# GEMINI.net
KiCad netlist of a schematic drawn in EAGLE
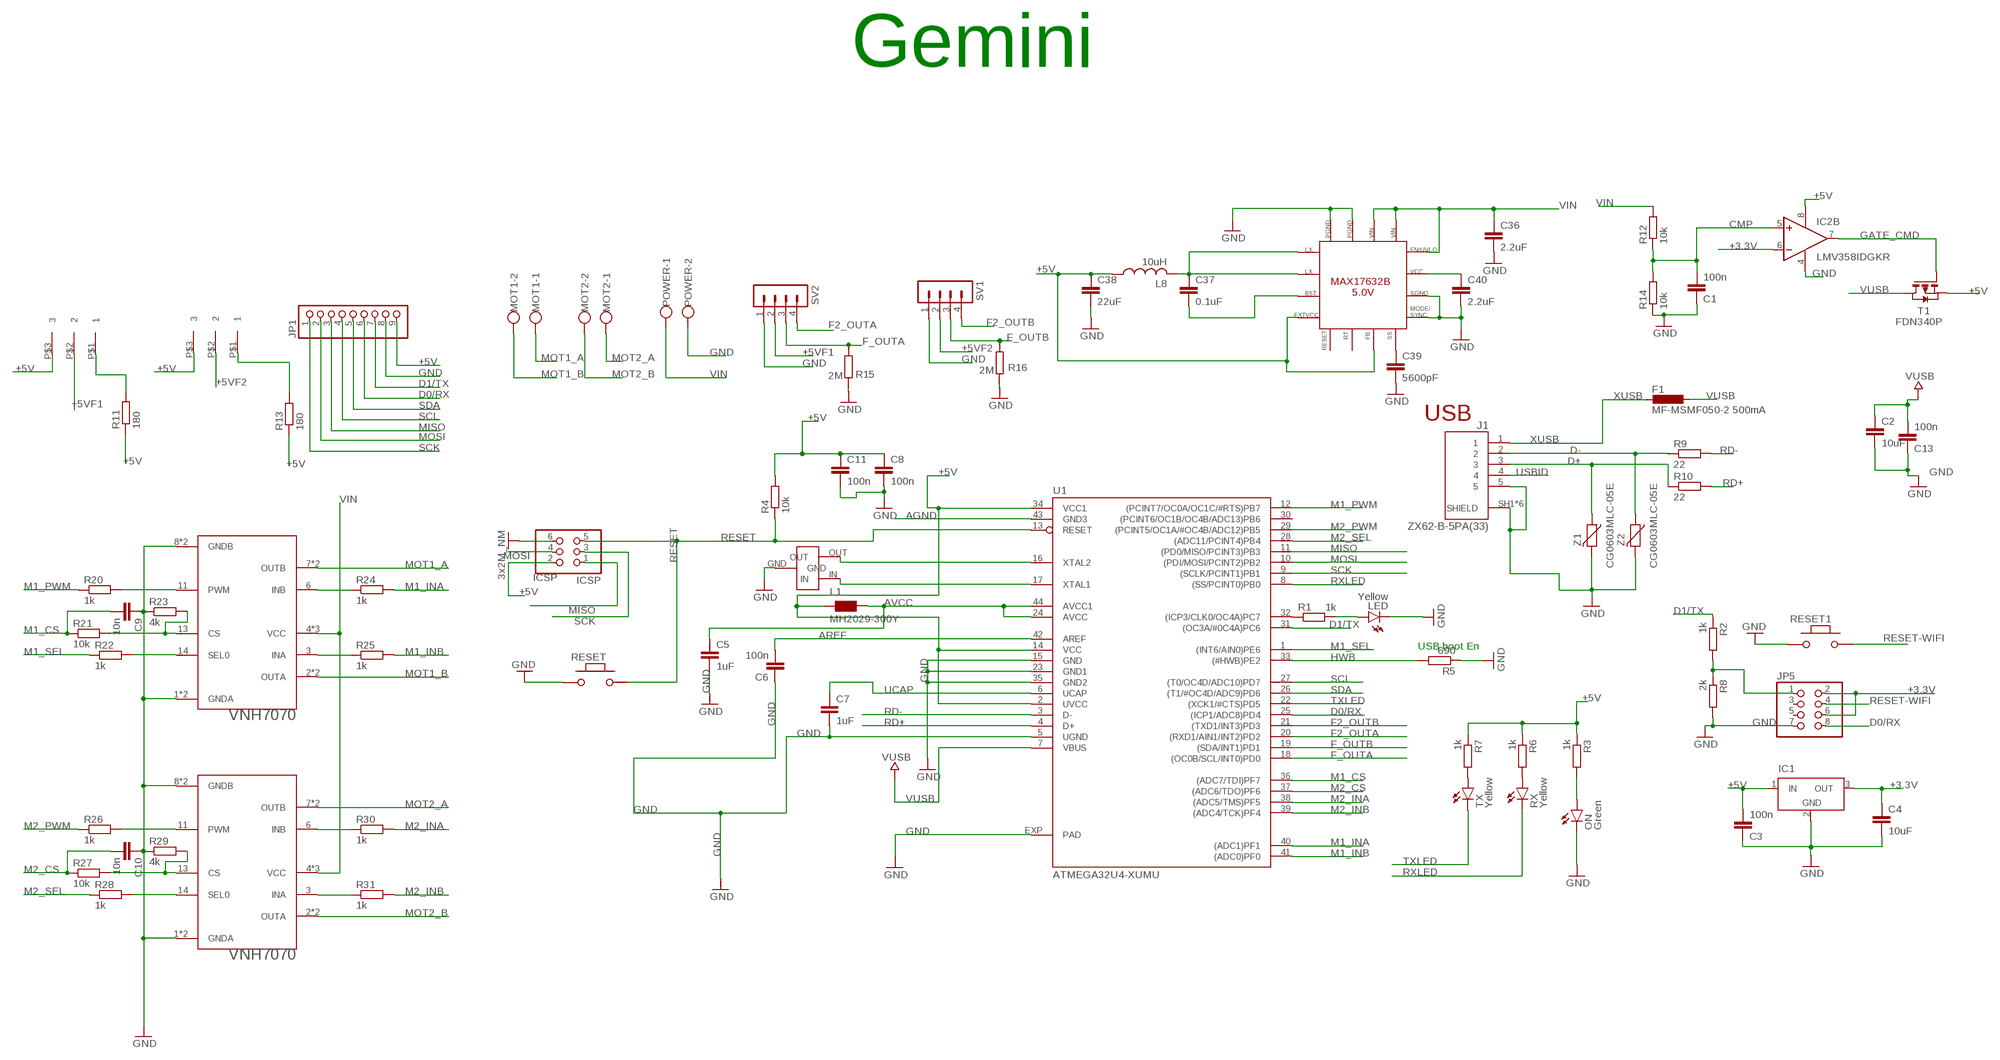
[diagram p0: schematic, sheet 1]

(export (version "E")
  (design (tool "Eeschema 10.0.6"))
  (components
    (comp (ref "C1")
      (value "100n")
      (footprint "eagle-import:C0402K")
      (libsource (lib "eagle-import") (part "rcl_334_C-EUC0402K"))
    )
    (comp (ref "C2")
      (value "10uF")
      (footprint "eagle-import:C0805")
      (libsource (lib "eagle-import") (part "rcl_334_C-EUC0805"))
    )
    (comp (ref "C3")
      (value "100n")
      (footprint "eagle-import:C0402K")
      (libsource (lib "eagle-import") (part "rcl_334_C-EUC0402K"))
    )
    (comp (ref "C4")
      (value "10uF")
      (footprint "eagle-import:C0805")
      (libsource (lib "eagle-import") (part "rcl_334_C-EUC0805"))
    )
    (comp (ref "C5")
      (value "1uF")
      (footprint "eagle-import:C0603-ROUND")
      (libsource (lib "eagle-import") (part "C-EUC0603"))
    )
    (comp (ref "C6")
      (value "100n")
      (footprint "eagle-import:C0402K")
      (libsource (lib "eagle-import") (part "rcl_334_C-EUC0402K"))
    )
    (comp (ref "C7")
      (value "1uF")
      (footprint "eagle-import:C0603-ROUND")
      (libsource (lib "eagle-import") (part "C-EUC0603"))
    )
    (comp (ref "C8")
      (value "100n")
      (footprint "eagle-import:C0402K")
      (libsource (lib "eagle-import") (part "rcl_334_C-EUC0402K"))
    )
    (comp (ref "C9")
      (value "10n")
      (footprint "eagle-import:C0402")
      (libsource (lib "eagle-import") (part "CC0402"))
    )
    (comp (ref "C10")
      (value "10n")
      (footprint "eagle-import:C0402")
      (libsource (lib "eagle-import") (part "CC0402"))
    )
    (comp (ref "C11")
      (value "100n")
      (footprint "eagle-import:C0402K")
      (libsource (lib "eagle-import") (part "rcl_334_C-EUC0402K"))
    )
    (comp (ref "C13")
      (value "100n")
      (footprint "eagle-import:C0402K")
      (libsource (lib "eagle-import") (part "rcl_334_C-EUC0402K"))
    )
    (comp (ref "C36")
      (value "2.2uF")
      (footprint "eagle-import:C0805")
      (libsource (lib "eagle-import") (part "rcl_334_C-EUC0805"))
    )
    (comp (ref "C37")
      (value "0.1uF")
      (footprint "eagle-import:C0805")
      (libsource (lib "eagle-import") (part "rcl_334_C-EUC0805"))
    )
    (comp (ref "C38")
      (value "22uF")
      (footprint "eagle-import:C0805")
      (libsource (lib "eagle-import") (part "rcl_334_C-EUC0805"))
    )
    (comp (ref "C39")
      (value "5600pF")
      (footprint "eagle-import:C0805")
      (libsource (lib "eagle-import") (part "rcl_334_C-EUC0805"))
    )
    (comp (ref "C40")
      (value "2.2uF")
      (footprint "eagle-import:C0805")
      (libsource (lib "eagle-import") (part "rcl_334_C-EUC0805"))
    )
    (comp (ref "F1")
      (value "MF-MSMF050-2 500mA")
      (footprint "eagle-import:L1812")
      (libsource (lib "eagle-import") (part "L-EUL1812"))
    )
    (comp (ref "IC1")
      (value "LT1129CST5")
      (footprint "eagle-import:SOT223")
      (fields (field (name "MPN") "LT1129CST-5#PBF"))
      (libsource (lib "eagle-import") (part "LT1129CST5"))
    )
    (comp (ref "IC2")
      (value "LMV358IDGKR")
      (footprint "eagle-import:MSOP08")
      (libsource (lib "eagle-import") (part "LMV358?MMX"))
    )
    (comp (ref "ICSP")
      (value "ICSP")
      (footprint "eagle-import:2X03")
      (libsource (lib "eagle-import") (part "PINHD-2X3"))
    )
    (comp (ref "J1")
      (value "ZX62-B-5PA(33)")
      (footprint "eagle-import:HRS_ZX62-B-5PA(33)")
      (fields (field (name "MF") "Hirose") (field (name "MP") "ZX62-B-5PA_33_"))
      (libsource (lib "eagle-import") (part "ZX62-B-5PA(33)"))
    )
    (comp (ref "JP1")
      (value "PINHD-1X9")
      (footprint "eagle-import:1X09-BIG")
      (libsource (lib "eagle-import") (part "PINHD-1X9"))
    )
    (comp (ref "JP5")
      (value "PINHD-2X4")
      (footprint "eagle-import:2X04")
      (libsource (lib "eagle-import") (part "PINHD-2X4"))
    )
    (comp (ref "L1")
      (value "MH2029-300Y")
      (footprint "eagle-import:0805")
      (libsource (lib "eagle-import") (part "WE-CBF_0805"))
    )
    (comp (ref "L8")
      (value "10uH")
      (footprint "eagle-import:RCL_L1812")
      (libsource (lib "eagle-import") (part "RCL_L-USL1812"))
    )
    (comp (ref "LED")
      (value "Yellow")
      (footprint "eagle-import:CHIPLED_0805")
      (libsource (lib "eagle-import") (part "LEDCHIPLED_0805"))
    )
    (comp (ref "MOT1")
      (value "W237-102")
      (footprint "eagle-import:W237-102")
      (fields (field (name "MPN") "237-102"))
      (libsource (lib "eagle-import") (part "W237-102"))
    )
    (comp (ref "MOT2")
      (value "W237-102")
      (footprint "eagle-import:W237-102")
      (fields (field (name "MPN") "237-102"))
      (libsource (lib "eagle-import") (part "W237-102"))
    )
    (comp (ref "ON")
      (value "Green")
      (footprint "eagle-import:CHIPLED_0805")
      (libsource (lib "eagle-import") (part "LEDCHIPLED_0805"))
    )
    (comp (ref "POWER")
      (value "W237-102")
      (footprint "eagle-import:W237-102")
      (fields (field (name "MPN") "237-102"))
      (libsource (lib "eagle-import") (part "W237-102"))
    )
    (comp (ref "R1")
      (value "1k")
      (footprint "eagle-import:R0402")
      (libsource (lib "eagle-import") (part "RR0402"))
    )
    (comp (ref "R2")
      (value "1k")
      (footprint "eagle-import:R0402")
      (libsource (lib "eagle-import") (part "RR0402"))
    )
    (comp (ref "R3")
      (value "1k")
      (footprint "eagle-import:R0402")
      (libsource (lib "eagle-import") (part "RR0402"))
    )
    (comp (ref "R4")
      (value "10k")
      (footprint "eagle-import:R0402")
      (libsource (lib "eagle-import") (part "RR0402"))
    )
    (comp (ref "R5")
      (value "690")
      (footprint "eagle-import:R0402")
      (libsource (lib "eagle-import") (part "RR0402"))
    )
    (comp (ref "R6")
      (value "1k")
      (footprint "eagle-import:R0402")
      (libsource (lib "eagle-import") (part "RR0402"))
    )
    (comp (ref "R7")
      (value "1k")
      (footprint "eagle-import:R0402")
      (libsource (lib "eagle-import") (part "RR0402"))
    )
    (comp (ref "R8")
      (value "2k")
      (footprint "eagle-import:R0402")
      (libsource (lib "eagle-import") (part "RR0402"))
    )
    (comp (ref "R9")
      (value "22")
      (footprint "eagle-import:R0402")
      (libsource (lib "eagle-import") (part "RR0402"))
    )
    (comp (ref "R10")
      (value "22")
      (footprint "eagle-import:R0402")
      (libsource (lib "eagle-import") (part "RR0402"))
    )
    (comp (ref "R11")
      (value "180")
      (footprint "eagle-import:R0402")
      (libsource (lib "eagle-import") (part "RR0402"))
    )
    (comp (ref "R12")
      (value "10k")
      (footprint "eagle-import:R0402")
      (libsource (lib "eagle-import") (part "RR0402"))
    )
    (comp (ref "R13")
      (value "180")
      (footprint "eagle-import:R0402")
      (libsource (lib "eagle-import") (part "RR0402"))
    )
    (comp (ref "R14")
      (value "10k")
      (footprint "eagle-import:R0402")
      (libsource (lib "eagle-import") (part "RR0402"))
    )
    (comp (ref "R15")
      (value "2M")
      (footprint "eagle-import:R0402")
      (libsource (lib "eagle-import") (part "RR0402"))
    )
    (comp (ref "R16")
      (value "2M")
      (footprint "eagle-import:R0402")
      (libsource (lib "eagle-import") (part "RR0402"))
    )
    (comp (ref "R20")
      (value "1k")
      (footprint "eagle-import:R0402")
      (libsource (lib "eagle-import") (part "RR0402"))
    )
    (comp (ref "R21")
      (value "10k")
      (footprint "eagle-import:R0402")
      (libsource (lib "eagle-import") (part "RR0402"))
    )
    (comp (ref "R22")
      (value "1k")
      (footprint "eagle-import:R0402")
      (libsource (lib "eagle-import") (part "RR0402"))
    )
    (comp (ref "R23")
      (value "4k")
      (footprint "eagle-import:R0402")
      (libsource (lib "eagle-import") (part "RR0402"))
    )
    (comp (ref "R24")
      (value "1k")
      (footprint "eagle-import:R0402")
      (libsource (lib "eagle-import") (part "RR0402"))
    )
    (comp (ref "R25")
      (value "1k")
      (footprint "eagle-import:R0402")
      (libsource (lib "eagle-import") (part "RR0402"))
    )
    (comp (ref "R26")
      (value "1k")
      (footprint "eagle-import:R0402")
      (libsource (lib "eagle-import") (part "RR0402"))
    )
    (comp (ref "R27")
      (value "10k")
      (footprint "eagle-import:R0402")
      (libsource (lib "eagle-import") (part "RR0402"))
    )
    (comp (ref "R28")
      (value "1k")
      (footprint "eagle-import:R0402")
      (libsource (lib "eagle-import") (part "RR0402"))
    )
    (comp (ref "R29")
      (value "4k")
      (footprint "eagle-import:R0402")
      (libsource (lib "eagle-import") (part "RR0402"))
    )
    (comp (ref "R30")
      (value "1k")
      (footprint "eagle-import:R0402")
      (libsource (lib "eagle-import") (part "RR0402"))
    )
    (comp (ref "R31")
      (value "1k")
      (footprint "eagle-import:R0402")
      (libsource (lib "eagle-import") (part "RR0402"))
    )
    (comp (ref "RESET")
      (value "MYSMD_PB157")
      (footprint "eagle-import:SMD_157SW")
      (libsource (lib "eagle-import") (part "MYSMD_PB157"))
    )
    (comp (ref "RESET1")
      (value "MYSMD_PB157")
      (footprint "eagle-import:SMD_157SW")
      (libsource (lib "eagle-import") (part "MYSMD_PB157"))
    )
    (comp (ref "RX")
      (value "Yellow")
      (footprint "eagle-import:CHIPLED_0805")
      (libsource (lib "eagle-import") (part "LEDCHIPLED_0805"))
    )
    (comp (ref "SV1")
      (value "MA04-1")
      (footprint "eagle-import:MA04-1")
      (libsource (lib "eagle-import") (part "MA04-1"))
    )
    (comp (ref "SV2")
      (value "MA04-1")
      (footprint "eagle-import:MA04-1")
      (libsource (lib "eagle-import") (part "MA04-1"))
    )
    (comp (ref "T1")
      (value "FDN340P")
      (footprint "eagle-import:SOT-23")
      (libsource (lib "eagle-import") (part "PMOSSOT23"))
    )
    (comp (ref "TX")
      (value "Yellow")
      (footprint "eagle-import:CHIPLED_0805")
      (libsource (lib "eagle-import") (part "LEDCHIPLED_0805"))
    )
    (comp (ref "U$1")
      (value "RISONATORE")
      (footprint "eagle-import:RISONATORE")
      (libsource (lib "eagle-import") (part "RISONATORE"))
    )
    (comp (ref "U$2")
      (value "2BRIDGE")
      (footprint "eagle-import:2BRIDGE")
      (libsource (lib "eagle-import") (part "2BRIDGE"))
    )
    (comp (ref "U$3")
      (value "MAX17632B")
      (footprint "eagle-import:QFN16")
      (libsource (lib "eagle-import") (part "MAX17632B"))
    )
    (comp (ref "U$4")
      (value "2BRIDGE")
      (footprint "eagle-import:2BRIDGE")
      (libsource (lib "eagle-import") (part "2BRIDGE"))
    )
    (comp (ref "U$29")
      (value "VNH7070")
      (footprint "eagle-import:SO16")
      (libsource (lib "eagle-import") (part "VNH7070"))
    )
    (comp (ref "U$32")
      (value "VNH7070")
      (footprint "eagle-import:SO16")
      (libsource (lib "eagle-import") (part "VNH7070"))
    )
    (comp (ref "U1")
      (value "ATMEGA32U4-XUMU")
      (footprint "eagle-import:QFN44ML7X7")
      (libsource (lib "eagle-import") (part "ATMEGA32U4-XUMU"))
    )
    (comp (ref "Z1")
      (value "CG0603MLC-05E")
      (footprint "eagle-import:CT_CN0603")
      (libsource (lib "eagle-import") (part "VARISTORCN0603"))
    )
    (comp (ref "Z2")
      (value "CG0603MLC-05E")
      (footprint "eagle-import:CT_CN0603")
      (libsource (lib "eagle-import") (part "VARISTORCN0603"))
    )
  )
  (nets
    (net (code "1") (name "/+3.3V") (class "Default")
      (node (ref "C4") (pin "1") (pinfunction "1_1") (pintype "passive"))
      (node (ref "IC1") (pin "3") (pinfunction "OUT_3") (pintype "output"))
      (node (ref "IC2") (pin "6") (pinfunction "-IN_6") (pintype "input"))
      (node (ref "JP5") (pin "2") (pinfunction "2_2") (pintype "passive"))
      (node (ref "JP5") (pin "6") (pinfunction "6_6") (pintype "passive"))
    )
    (net (code "2") (name "/+5V") (class "Default")
      (node (ref "C11") (pin "1") (pinfunction "1_1") (pintype "passive"))
      (node (ref "C3") (pin "2") (pinfunction "2_2") (pintype "passive"))
      (node (ref "C38") (pin "1") (pinfunction "1_1") (pintype "passive"))
      (node (ref "C8") (pin "1") (pinfunction "1_1") (pintype "passive"))
      (node (ref "IC1") (pin "1") (pinfunction "IN_1") (pintype "input"))
      (node (ref "IC2") (pin "8") (pinfunction "V+_8") (pintype "power_in"))
      (node (ref "ICSP") (pin "2") (pinfunction "2_2") (pintype "passive"))
      (node (ref "JP1") (pin "9") (pinfunction "9_9") (pintype "passive"))
      (node (ref "L1") (pin "1") (pinfunction "1_1") (pintype "passive"))
      (node (ref "L8") (pin "1") (pinfunction "1_1") (pintype "passive"))
      (node (ref "R11") (pin "1") (pinfunction "1_1") (pintype "passive"))
      (node (ref "R13") (pin "1") (pinfunction "1_1") (pintype "passive"))
      (node (ref "R3") (pin "1") (pinfunction "1_1") (pintype "passive"))
      (node (ref "R4") (pin "2") (pinfunction "2_2") (pintype "passive"))
      (node (ref "R6") (pin "1") (pinfunction "1_1") (pintype "passive"))
      (node (ref "R7") (pin "1") (pinfunction "1_1") (pintype "passive"))
      (node (ref "T1") (pin "2") (pinfunction "S_2") (pintype "passive"))
      (node (ref "U$2") (pin "P$3") (pinfunction "3_P$3") (pintype "bidirectional"))
      (node (ref "U$3") (pin "6") (pinfunction "FB_6") (pintype "bidirectional"))
      (node (ref "U$3") (pin "9") (pinfunction "EXTVCC_9") (pintype "bidirectional"))
      (node (ref "U$4") (pin "P$3") (pinfunction "3_P$3") (pintype "bidirectional"))
      (node (ref "U1") (pin "14") (pinfunction "VCC_14") (pintype "power_in"))
      (node (ref "U1") (pin "2") (pinfunction "UVCC_2") (pintype "power_in"))
      (node (ref "U1") (pin "34") (pinfunction "VCC1_34") (pintype "power_in"))
    )
    (net (code "3") (name "/+5VF1") (class "Default")
      (node (ref "SV2") (pin "2") (pinfunction "2_2") (pintype "passive"))
      (node (ref "U$2") (pin "P$2") (pinfunction "2_P$2") (pintype "bidirectional"))
    )
    (net (code "4") (name "/+5VF2") (class "Default")
      (node (ref "SV1") (pin "2") (pinfunction "2_2") (pintype "passive"))
      (node (ref "U$4") (pin "P$2") (pinfunction "2_P$2") (pintype "bidirectional"))
    )
    (net (code "5") (name "/AGND") (class "Default")
      (node (ref "U1") (pin "43") (pinfunction "GND3_43") (pintype "power_in"))
    )
    (net (code "6") (name "/AREF") (class "Default")
      (node (ref "C6") (pin "2") (pinfunction "2_2") (pintype "passive"))
      (node (ref "U1") (pin "42") (pinfunction "AREF_42") (pintype "power_in"))
    )
    (net (code "7") (name "/AVCC") (class "Default")
      (node (ref "C5") (pin "1") (pinfunction "1_1") (pintype "passive"))
      (node (ref "L1") (pin "2") (pinfunction "2_2") (pintype "passive"))
      (node (ref "U1") (pin "24") (pinfunction "AVCC_24") (pintype "power_in"))
      (node (ref "U1") (pin "44") (pinfunction "AVCC1_44") (pintype "power_in"))
    )
    (net (code "8") (name "/CMP") (class "Default")
      (node (ref "C1") (pin "2") (pinfunction "2_2") (pintype "passive"))
      (node (ref "IC2") (pin "5") (pinfunction "+IN_5") (pintype "input"))
      (node (ref "R12") (pin "1") (pinfunction "1_1") (pintype "passive"))
      (node (ref "R14") (pin "2") (pinfunction "2_2") (pintype "passive"))
    )
    (net (code "9") (name "/D+") (class "Default")
      (node (ref "J1") (pin "3") (pinfunction "3_3") (pintype "passive"))
      (node (ref "R10") (pin "1") (pinfunction "1_1") (pintype "passive"))
      (node (ref "Z1") (pin "1") (pinfunction "1_1") (pintype "passive"))
    )
    (net (code "10") (name "/D-") (class "Default")
      (node (ref "J1") (pin "2") (pinfunction "2_2") (pintype "passive"))
      (node (ref "R9") (pin "1") (pinfunction "1_1") (pintype "passive"))
      (node (ref "Z2") (pin "1") (pinfunction "1_1") (pintype "passive"))
    )
    (net (code "11") (name "/D0{slash}RX") (class "Default")
      (node (ref "JP1") (pin "6") (pinfunction "6_6") (pintype "passive"))
      (node (ref "JP5") (pin "8") (pinfunction "8_8") (pintype "passive"))
      (node (ref "U1") (pin "25") (pinfunction "(ICP1/ADC8)PD4_25") (pintype "bidirectional"))
    )
    (net (code "12") (name "/D1{slash}TX") (class "Default")
      (node (ref "JP1") (pin "7") (pinfunction "7_7") (pintype "passive"))
      (node (ref "R2") (pin "1") (pinfunction "1_1") (pintype "passive"))
      (node (ref "U1") (pin "31") (pinfunction "(OC3A/#0C4A)PC6_31") (pintype "bidirectional"))
    )
    (net (code "13") (name "/F2_OUTA") (class "Default")
      (node (ref "SV2") (pin "4") (pinfunction "4_4") (pintype "passive"))
      (node (ref "U1") (pin "20") (pinfunction "(RXD1/AIN1/INT2)PD2_20") (pintype "bidirectional"))
    )
    (net (code "14") (name "/F2_OUTB") (class "Default")
      (node (ref "SV1") (pin "4") (pinfunction "4_4") (pintype "passive"))
      (node (ref "U1") (pin "21") (pinfunction "(TXD1/INT3)PD3_21") (pintype "bidirectional"))
    )
    (net (code "15") (name "/F_OUTA") (class "Default")
      (node (ref "R15") (pin "1") (pinfunction "1_1") (pintype "passive"))
      (node (ref "SV2") (pin "3") (pinfunction "3_3") (pintype "passive"))
      (node (ref "U1") (pin "18") (pinfunction "(OC0B/SCL/INT0)PD0_18") (pintype "bidirectional"))
    )
    (net (code "16") (name "/F_OUTB") (class "Default")
      (node (ref "R16") (pin "1") (pinfunction "1_1") (pintype "passive"))
      (node (ref "SV1") (pin "3") (pinfunction "3_3") (pintype "passive"))
      (node (ref "U1") (pin "19") (pinfunction "(SDA/INT1)PD1_19") (pintype "bidirectional"))
    )
    (net (code "17") (name "/GATE_CMD") (class "Default")
      (node (ref "IC2") (pin "7") (pinfunction "OUT_7") (pintype "output"))
      (node (ref "T1") (pin "3") (pinfunction "G_3") (pintype "passive"))
    )
    (net (code "18") (name "/HWB") (class "Default")
      (node (ref "R5") (pin "2") (pinfunction "2_2") (pintype "passive"))
      (node (ref "U1") (pin "33") (pinfunction "(#HWB)PE2_33") (pintype "bidirectional"))
    )
    (net (code "19") (name "/M1_CS") (class "Default")
      (node (ref "C9") (pin "2") (pinfunction "2_2") (pintype "passive"))
      (node (ref "R21") (pin "1") (pinfunction "1_1") (pintype "passive"))
      (node (ref "U1") (pin "36") (pinfunction "(ADC7/TDI)PF7_36") (pintype "bidirectional"))
    )
    (net (code "20") (name "/M1_INA") (class "Default")
      (node (ref "R24") (pin "2") (pinfunction "2_2") (pintype "passive"))
      (node (ref "U1") (pin "40") (pinfunction "(ADC1)PF1_40") (pintype "bidirectional"))
    )
    (net (code "21") (name "/M1_INB") (class "Default")
      (node (ref "R25") (pin "2") (pinfunction "2_2") (pintype "passive"))
      (node (ref "U1") (pin "41") (pinfunction "(ADC0)PF0_41") (pintype "bidirectional"))
    )
    (net (code "22") (name "/M1_PWM") (class "Default")
      (node (ref "R20") (pin "1") (pinfunction "1_1") (pintype "passive"))
      (node (ref "U1") (pin "12") (pinfunction "(PCINT7/OC0A/OC1C/#RTS)PB7_12") (pintype "bidirectional"))
    )
    (net (code "23") (name "/M1_SEL") (class "Default")
      (node (ref "R22") (pin "1") (pinfunction "1_1") (pintype "passive"))
      (node (ref "U1") (pin "1") (pinfunction "(INT6/AIN0)PE6_1") (pintype "bidirectional"))
    )
    (net (code "24") (name "/M2_CS") (class "Default")
      (node (ref "C10") (pin "2") (pinfunction "2_2") (pintype "passive"))
      (node (ref "R27") (pin "1") (pinfunction "1_1") (pintype "passive"))
      (node (ref "U1") (pin "37") (pinfunction "(ADC6/TDO)PF6_37") (pintype "bidirectional"))
    )
    (net (code "25") (name "/M2_INA") (class "Default")
      (node (ref "R30") (pin "2") (pinfunction "2_2") (pintype "passive"))
      (node (ref "U1") (pin "38") (pinfunction "(ADC5/TMS)PF5_38") (pintype "bidirectional"))
    )
    (net (code "26") (name "/M2_INB") (class "Default")
      (node (ref "R31") (pin "2") (pinfunction "2_2") (pintype "passive"))
      (node (ref "U1") (pin "39") (pinfunction "(ADC4/TCK)PF4_39") (pintype "bidirectional"))
    )
    (net (code "27") (name "/M2_PWM") (class "Default")
      (node (ref "R26") (pin "1") (pinfunction "1_1") (pintype "passive"))
      (node (ref "U1") (pin "29") (pinfunction "(PCINT5/OC1A/#OC4B/ADC12)PB5_29") (pintype "bidirectional"))
    )
    (net (code "28") (name "/M2_SEL") (class "Default")
      (node (ref "R28") (pin "1") (pinfunction "1_1") (pintype "passive"))
      (node (ref "U1") (pin "28") (pinfunction "(ADC11/PCINT4)PB4_28") (pintype "bidirectional"))
    )
    (net (code "29") (name "/MISO") (class "Default")
      (node (ref "ICSP") (pin "1") (pinfunction "1_1") (pintype "passive"))
      (node (ref "JP1") (pin "3") (pinfunction "3_3") (pintype "passive"))
      (node (ref "U1") (pin "11") (pinfunction "(PD0/MISO/PCINT3)PB3_11") (pintype "bidirectional"))
    )
    (net (code "30") (name "/MOSI") (class "Default")
      (node (ref "ICSP") (pin "4") (pinfunction "4_4") (pintype "passive"))
      (node (ref "JP1") (pin "2") (pinfunction "2_2") (pintype "passive"))
      (node (ref "U1") (pin "10") (pinfunction "(PDI/MOSI/PCINT2)PB2_10") (pintype "bidirectional"))
    )
    (net (code "31") (name "/MOT1_A") (class "Default")
      (node (ref "MOT1") (pin "1") (pinfunction "KL_1") (pintype "passive"))
      (node (ref "U$29") (pin "10") (pinfunction "OUTB_10") (pintype "bidirectional"))
      (node (ref "U$29") (pin "7") (pinfunction "OUTB_7") (pintype "bidirectional"))
    )
    (net (code "32") (name "/MOT1_B") (class "Default")
      (node (ref "MOT1") (pin "2") (pinfunction "KL_2") (pintype "passive"))
      (node (ref "U$29") (pin "15") (pinfunction "OUTA_15") (pintype "bidirectional"))
      (node (ref "U$29") (pin "2") (pinfunction "OUTA_2") (pintype "bidirectional"))
    )
    (net (code "33") (name "/MOT2_A") (class "Default")
      (node (ref "MOT2") (pin "1") (pinfunction "KL_1") (pintype "passive"))
      (node (ref "U$32") (pin "10") (pinfunction "OUTB_10") (pintype "bidirectional"))
      (node (ref "U$32") (pin "7") (pinfunction "OUTB_7") (pintype "bidirectional"))
    )
    (net (code "34") (name "/MOT2_B") (class "Default")
      (node (ref "MOT2") (pin "2") (pinfunction "KL_2") (pintype "passive"))
      (node (ref "U$32") (pin "15") (pinfunction "OUTA_15") (pintype "bidirectional"))
      (node (ref "U$32") (pin "2") (pinfunction "OUTA_2") (pintype "bidirectional"))
    )
    (net (code "35") (name "/RD+") (class "Default")
      (node (ref "R10") (pin "2") (pinfunction "2_2") (pintype "passive"))
      (node (ref "U1") (pin "4") (pinfunction "D+_4") (pintype "bidirectional"))
    )
    (net (code "36") (name "/RD-") (class "Default")
      (node (ref "R9") (pin "2") (pinfunction "2_2") (pintype "passive"))
      (node (ref "U1") (pin "3") (pinfunction "D-_3") (pintype "bidirectional"))
    )
    (net (code "37") (name "/RESET") (class "Default")
      (node (ref "ICSP") (pin "5") (pinfunction "5_5") (pintype "passive"))
      (node (ref "R4") (pin "1") (pinfunction "1_1") (pintype "passive"))
      (node (ref "RESET") (pin "1") (pinfunction "1_1") (pintype "passive"))
      (node (ref "U1") (pin "13") (pinfunction "RESET_13") (pintype "input"))
    )
    (net (code "38") (name "/RESET-WIFI") (class "Default")
      (node (ref "JP5") (pin "4") (pinfunction "4_4") (pintype "passive"))
      (node (ref "RESET1") (pin "1") (pinfunction "1_1") (pintype "passive"))
    )
    (net (code "39") (name "/RXLED") (class "Default")
      (node (ref "RX") (pin "C") (pinfunction "C_C") (pintype "passive"))
      (node (ref "U1") (pin "8") (pinfunction "(SS/PCINT0)PB0_8") (pintype "bidirectional"))
    )
    (net (code "40") (name "/SCK") (class "Default")
      (node (ref "ICSP") (pin "3") (pinfunction "3_3") (pintype "passive"))
      (node (ref "JP1") (pin "1") (pinfunction "1_1") (pintype "passive"))
      (node (ref "U1") (pin "9") (pinfunction "(SCLK/PCINT1)PB1_9") (pintype "bidirectional"))
    )
    (net (code "41") (name "/SCL") (class "Default")
      (node (ref "JP1") (pin "4") (pinfunction "4_4") (pintype "passive"))
      (node (ref "U1") (pin "27") (pinfunction "(T0/OC4D/ADC10)PD7_27") (pintype "bidirectional"))
    )
    (net (code "42") (name "/SDA") (class "Default")
      (node (ref "JP1") (pin "5") (pinfunction "5_5") (pintype "passive"))
      (node (ref "U1") (pin "26") (pinfunction "(T1/#OC4D/ADC9)PD6_26") (pintype "bidirectional"))
    )
    (net (code "43") (name "/TXLED") (class "Default")
      (node (ref "TX") (pin "C") (pinfunction "C_C") (pintype "passive"))
      (node (ref "U1") (pin "22") (pinfunction "(XCK1/#CTS)PD5_22") (pintype "bidirectional"))
    )
    (net (code "44") (name "/UCAP") (class "Default")
      (node (ref "C7") (pin "1") (pinfunction "1_1") (pintype "passive"))
      (node (ref "U1") (pin "6") (pinfunction "UCAP_6") (pintype "passive"))
    )
    (net (code "45") (name "/USBID") (class "Default")
      (node (ref "J1") (pin "4") (pinfunction "4_4") (pintype "passive"))
    )
    (net (code "46") (name "/VIN") (class "Default")
      (node (ref "C36") (pin "1") (pinfunction "1_1") (pintype "passive"))
      (node (ref "POWER") (pin "1") (pinfunction "KL_1") (pintype "passive"))
      (node (ref "R12") (pin "2") (pinfunction "2_2") (pintype "passive"))
      (node (ref "U$29") (pin "12") (pinfunction "VCC_12") (pintype "bidirectional"))
      (node (ref "U$29") (pin "4") (pinfunction "VCC_4") (pintype "bidirectional"))
      (node (ref "U$29") (pin "5") (pinfunction "VCC_5") (pintype "bidirectional"))
      (node (ref "U$3") (pin "1") (pinfunction "ENUVLO_1") (pintype "bidirectional"))
      (node (ref "U$3") (pin "15") (pinfunction "VIN1_15") (pintype "bidirectional"))
      (node (ref "U$3") (pin "16") (pinfunction "VIN2_16") (pintype "bidirectional"))
      (node (ref "U$32") (pin "12") (pinfunction "VCC_12") (pintype "bidirectional"))
      (node (ref "U$32") (pin "4") (pinfunction "VCC_4") (pintype "bidirectional"))
      (node (ref "U$32") (pin "5") (pinfunction "VCC_5") (pintype "bidirectional"))
    )
    (net (code "47") (name "/XUSB") (class "Default")
      (node (ref "F1") (pin "2") (pinfunction "2_2") (pintype "passive"))
      (node (ref "J1") (pin "1") (pinfunction "1_1") (pintype "passive"))
    )
    (net (code "48") (name "3x2M_NM") (class "Default")
      (node (ref "C1") (pin "1") (pinfunction "1_1") (pintype "passive"))
      (node (ref "C10") (pin "1") (pinfunction "1_1") (pintype "passive"))
      (node (ref "C11") (pin "2") (pinfunction "2_2") (pintype "passive"))
      (node (ref "C13") (pin "1") (pinfunction "1_1") (pintype "passive"))
      (node (ref "C2") (pin "2") (pinfunction "2_2") (pintype "passive"))
      (node (ref "C3") (pin "1") (pinfunction "1_1") (pintype "passive"))
      (node (ref "C36") (pin "2") (pinfunction "2_2") (pintype "passive"))
      (node (ref "C38") (pin "2") (pinfunction "2_2") (pintype "passive"))
      (node (ref "C39") (pin "2") (pinfunction "2_2") (pintype "passive"))
      (node (ref "C4") (pin "2") (pinfunction "2_2") (pintype "passive"))
      (node (ref "C40") (pin "2") (pinfunction "2_2") (pintype "passive"))
      (node (ref "C5") (pin "2") (pinfunction "2_2") (pintype "passive"))
      (node (ref "C6") (pin "1") (pinfunction "1_1") (pintype "passive"))
      (node (ref "C7") (pin "2") (pinfunction "2_2") (pintype "passive"))
      (node (ref "C8") (pin "2") (pinfunction "2_2") (pintype "passive"))
      (node (ref "C9") (pin "1") (pinfunction "1_1") (pintype "passive"))
      (node (ref "IC1") (pin "2") (pinfunction "GND_2") (pintype "power_in"))
      (node (ref "IC2") (pin "4") (pinfunction "V-_4") (pintype "power_in"))
      (node (ref "ICSP") (pin "6") (pinfunction "6_6") (pintype "passive"))
      (node (ref "J1") (pin "5") (pinfunction "5_5") (pintype "passive"))
      (node (ref "J1") (pin "SH1") (pinfunction "SHIELD_SH1") (pintype "passive"))
      (node (ref "J1") (pin "SH2") (pinfunction "SHIELD_SH2") (pintype "passive"))
      (node (ref "J1") (pin "SH3") (pinfunction "SHIELD_SH3") (pintype "passive"))
      (node (ref "J1") (pin "SH4") (pinfunction "SHIELD_SH4") (pintype "passive"))
      (node (ref "J1") (pin "SH5") (pinfunction "SHIELD_SH5") (pintype "passive"))
      (node (ref "J1") (pin "SH6") (pinfunction "SHIELD_SH6") (pintype "passive"))
      (node (ref "JP1") (pin "8") (pinfunction "8_8") (pintype "passive"))
      (node (ref "JP5") (pin "7") (pinfunction "7_7") (pintype "passive"))
      (node (ref "LED") (pin "C") (pinfunction "C_C") (pintype "passive"))
      (node (ref "ON") (pin "C") (pinfunction "C_C") (pintype "passive"))
      (node (ref "POWER") (pin "2") (pinfunction "KL_2") (pintype "passive"))
      (node (ref "R14") (pin "1") (pinfunction "1_1") (pintype "passive"))
      (node (ref "R15") (pin "2") (pinfunction "2_2") (pintype "passive"))
      (node (ref "R16") (pin "2") (pinfunction "2_2") (pintype "passive"))
      (node (ref "R23") (pin "1") (pinfunction "1_1") (pintype "passive"))
      (node (ref "R29") (pin "1") (pinfunction "1_1") (pintype "passive"))
      (node (ref "R5") (pin "1") (pinfunction "1_1") (pintype "passive"))
      (node (ref "R8") (pin "2") (pinfunction "2_2") (pintype "passive"))
      (node (ref "RESET") (pin "2") (pinfunction "2_2") (pintype "passive"))
      (node (ref "RESET1") (pin "2") (pinfunction "2_2") (pintype "passive"))
      (node (ref "SV1") (pin "1") (pinfunction "1_1") (pintype "passive"))
      (node (ref "SV2") (pin "1") (pinfunction "1_1") (pintype "passive"))
      (node (ref "U$1") (pin "GND") (pinfunction "GND_GND") (pintype "bidirectional"))
      (node (ref "U$29") (pin "1") (pinfunction "GNDA_1") (pintype "bidirectional"))
      (node (ref "U$29") (pin "16") (pinfunction "GNDA_16") (pintype "bidirectional"))
      (node (ref "U$29") (pin "8") (pinfunction "GNDB_8") (pintype "bidirectional"))
      (node (ref "U$29") (pin "9") (pinfunction "GNDB_9") (pintype "bidirectional"))
      (node (ref "U$3") (pin "13") (pinfunction "PGND1_13") (pintype "bidirectional"))
      (node (ref "U$3") (pin "14") (pinfunction "PGND2_14") (pintype "bidirectional"))
      (node (ref "U$3") (pin "3") (pinfunction "SGND_3") (pintype "bidirectional"))
      (node (ref "U$3") (pin "4") (pinfunction "MODESYNC_4") (pintype "bidirectional"))
      (node (ref "U$32") (pin "1") (pinfunction "GNDA_1") (pintype "bidirectional"))
      (node (ref "U$32") (pin "16") (pinfunction "GNDA_16") (pintype "bidirectional"))
      (node (ref "U$32") (pin "8") (pinfunction "GNDB_8") (pintype "bidirectional"))
      (node (ref "U$32") (pin "9") (pinfunction "GNDB_9") (pintype "bidirectional"))
      (node (ref "U1") (pin "15") (pinfunction "GND_15") (pintype "power_in"))
      (node (ref "U1") (pin "23") (pinfunction "GND1_23") (pintype "power_in"))
      (node (ref "U1") (pin "35") (pinfunction "GND2_35") (pintype "power_in"))
      (node (ref "U1") (pin "5") (pinfunction "UGND_5") (pintype "power_in"))
      (node (ref "U1") (pin "EXP") (pinfunction "PAD_EXP") (pintype "power_in"))
      (node (ref "Z1") (pin "2") (pinfunction "2_2") (pintype "passive"))
      (node (ref "Z2") (pin "2") (pinfunction "2_2") (pintype "passive"))
    )
    (net (code "49") (name "Net-(JP5-Pad1)") (class "Default")
      (node (ref "JP5") (pin "1") (pinfunction "1_1") (pintype "passive"))
      (node (ref "R2") (pin "2") (pinfunction "2_2") (pintype "passive"))
      (node (ref "R8") (pin "1") (pinfunction "1_1") (pintype "passive"))
    )
    (net (code "50") (name "Net-(LED-PadA)") (class "Default")
      (node (ref "LED") (pin "A") (pinfunction "A_A") (pintype "passive"))
      (node (ref "R1") (pin "2") (pinfunction "2_2") (pintype "passive"))
    )
    (net (code "51") (name "Net-(ON-PadA)") (class "Default")
      (node (ref "ON") (pin "A") (pinfunction "A_A") (pintype "passive"))
      (node (ref "R3") (pin "2") (pinfunction "2_2") (pintype "passive"))
    )
    (net (code "52") (name "Net-(R6-Pad2)") (class "Default")
      (node (ref "R6") (pin "2") (pinfunction "2_2") (pintype "passive"))
      (node (ref "RX") (pin "A") (pinfunction "A_A") (pintype "passive"))
    )
    (net (code "53") (name "Net-(R7-Pad2)") (class "Default")
      (node (ref "R7") (pin "2") (pinfunction "2_2") (pintype "passive"))
      (node (ref "TX") (pin "A") (pinfunction "A_A") (pintype "passive"))
    )
    (net (code "54") (name "Net-(U$2-1)") (class "Default")
      (node (ref "R11") (pin "2") (pinfunction "2_2") (pintype "passive"))
      (node (ref "U$2") (pin "P$1") (pinfunction "1_P$1") (pintype "bidirectional"))
    )
    (net (code "55") (name "Net-(U$3-BST)") (class "Default")
      (node (ref "C37") (pin "2") (pinfunction "2_2") (pintype "passive"))
      (node (ref "U$3") (pin "10") (pinfunction "BST_10") (pintype "bidirectional"))
    )
    (net (code "56") (name "Net-(U$3-LX1)") (class "Default")
      (node (ref "C37") (pin "1") (pinfunction "1_1") (pintype "passive"))
      (node (ref "L8") (pin "2") (pinfunction "2_2") (pintype "passive"))
      (node (ref "U$3") (pin "11") (pinfunction "LX1_11") (pintype "bidirectional"))
      (node (ref "U$3") (pin "12") (pinfunction "LX2_12") (pintype "bidirectional"))
    )
    (net (code "57") (name "Net-(U$3-SS)") (class "Default")
      (node (ref "C39") (pin "1") (pinfunction "1_1") (pintype "passive"))
      (node (ref "U$3") (pin "5") (pinfunction "SS_5") (pintype "bidirectional"))
    )
    (net (code "58") (name "Net-(U$3-VCC)") (class "Default")
      (node (ref "C40") (pin "1") (pinfunction "1_1") (pintype "passive"))
      (node (ref "U$3") (pin "2") (pinfunction "VCC_2") (pintype "bidirectional"))
    )
    (net (code "59") (name "Net-(U$4-1)") (class "Default")
      (node (ref "R13") (pin "2") (pinfunction "2_2") (pintype "passive"))
      (node (ref "U$4") (pin "P$1") (pinfunction "1_P$1") (pintype "bidirectional"))
    )
    (net (code "60") (name "Net-(U$29-CS)") (class "Default")
      (node (ref "R21") (pin "2") (pinfunction "2_2") (pintype "passive"))
      (node (ref "R23") (pin "2") (pinfunction "2_2") (pintype "passive"))
      (node (ref "U$29") (pin "13") (pinfunction "CS_13") (pintype "bidirectional"))
    )
    (net (code "61") (name "Net-(U$29-INA)") (class "Default")
      (node (ref "R25") (pin "1") (pinfunction "1_1") (pintype "passive"))
      (node (ref "U$29") (pin "3") (pinfunction "INA_3") (pintype "bidirectional"))
    )
    (net (code "62") (name "Net-(U$29-INB)") (class "Default")
      (node (ref "R24") (pin "1") (pinfunction "1_1") (pintype "passive"))
      (node (ref "U$29") (pin "6") (pinfunction "INB_6") (pintype "bidirectional"))
    )
    (net (code "63") (name "Net-(U$29-PWM)") (class "Default")
      (node (ref "R20") (pin "2") (pinfunction "2_2") (pintype "passive"))
      (node (ref "U$29") (pin "11") (pinfunction "PWM_11") (pintype "bidirectional"))
    )
    (net (code "64") (name "Net-(U$29-SEL0)") (class "Default")
      (node (ref "R22") (pin "2") (pinfunction "2_2") (pintype "passive"))
      (node (ref "U$29") (pin "14") (pinfunction "SEL0_14") (pintype "bidirectional"))
    )
    (net (code "65") (name "Net-(U$32-CS)") (class "Default")
      (node (ref "R27") (pin "2") (pinfunction "2_2") (pintype "passive"))
      (node (ref "R29") (pin "2") (pinfunction "2_2") (pintype "passive"))
      (node (ref "U$32") (pin "13") (pinfunction "CS_13") (pintype "bidirectional"))
    )
    (net (code "66") (name "Net-(U$32-INA)") (class "Default")
      (node (ref "R31") (pin "1") (pinfunction "1_1") (pintype "passive"))
      (node (ref "U$32") (pin "3") (pinfunction "INA_3") (pintype "bidirectional"))
    )
    (net (code "67") (name "Net-(U$32-INB)") (class "Default")
      (node (ref "R30") (pin "1") (pinfunction "1_1") (pintype "passive"))
      (node (ref "U$32") (pin "6") (pinfunction "INB_6") (pintype "bidirectional"))
    )
    (net (code "68") (name "Net-(U$32-PWM)") (class "Default")
      (node (ref "R26") (pin "2") (pinfunction "2_2") (pintype "passive"))
      (node (ref "U$32") (pin "11") (pinfunction "PWM_11") (pintype "bidirectional"))
    )
    (net (code "69") (name "Net-(U$32-SEL0)") (class "Default")
      (node (ref "R28") (pin "2") (pinfunction "2_2") (pintype "passive"))
      (node (ref "U$32") (pin "14") (pinfunction "SEL0_14") (pintype "bidirectional"))
    )
    (net (code "70") (name "Net-(U1-(ICP3{slash}CLK0{slash}OC4A)PC7)") (class "Default")
      (node (ref "R1") (pin "1") (pinfunction "1_1") (pintype "passive"))
      (node (ref "U1") (pin "32") (pinfunction "(ICP3/CLK0/OC4A)PC7_32") (pintype "bidirectional"))
    )
    (net (code "71") (name "Net-(U1-XTAL1)") (class "Default")
      (node (ref "U$1") (pin "IN") (pinfunction "IN_IN") (pintype "bidirectional"))
      (node (ref "U1") (pin "17") (pinfunction "XTAL1_17") (pintype "bidirectional"))
    )
    (net (code "72") (name "Net-(U1-XTAL2)") (class "Default")
      (node (ref "U$1") (pin "OUT") (pinfunction "OUT_OUT") (pintype "bidirectional"))
      (node (ref "U1") (pin "16") (pinfunction "XTAL2_16") (pintype "bidirectional"))
    )
    (net (code "73") (name "VUSB") (class "Default")
      (node (ref "C13") (pin "2") (pinfunction "2_2") (pintype "passive"))
      (node (ref "C2") (pin "1") (pinfunction "1_1") (pintype "passive"))
      (node (ref "F1") (pin "1") (pinfunction "1_1") (pintype "passive"))
      (node (ref "T1") (pin "1") (pinfunction "D_1") (pintype "passive"))
      (node (ref "U1") (pin "7") (pinfunction "VBUS_7") (pintype "input"))
    )
    (net (code "74") (name "unconnected-(JP5-Pad3)") (class "Default")
      (node (ref "JP5") (pin "3") (pinfunction "3_3") (pintype "passive"))
    )
    (net (code "75") (name "unconnected-(JP5-Pad5)") (class "Default")
      (node (ref "JP5") (pin "5") (pinfunction "5_5") (pintype "passive"))
    )
    (net (code "76") (name "unconnected-(U$3-RESET-Pad8)") (class "Default")
      (node (ref "U$3") (pin "8") (pinfunction "RESET_8") (pintype "bidirectional"))
    )
    (net (code "77") (name "unconnected-(U$3-RT-Pad7)") (class "Default")
      (node (ref "U$3") (pin "7") (pinfunction "RT_7") (pintype "bidirectional"))
    )
    (net (code "78") (name "unconnected-(U1-(PCINT6{slash}OC1B{slash}OC4B{slash}ADC13)PB6-Pad30)") (class "Default")
      (node (ref "U1") (pin "30") (pinfunction "(PCINT6/OC1B/OC4B/ADC13)PB6_30") (pintype "bidirectional"))
    )
  )
)
